# FPGA_7A35T.net
KiCad netlist of a schematic drawn in Altium Designer
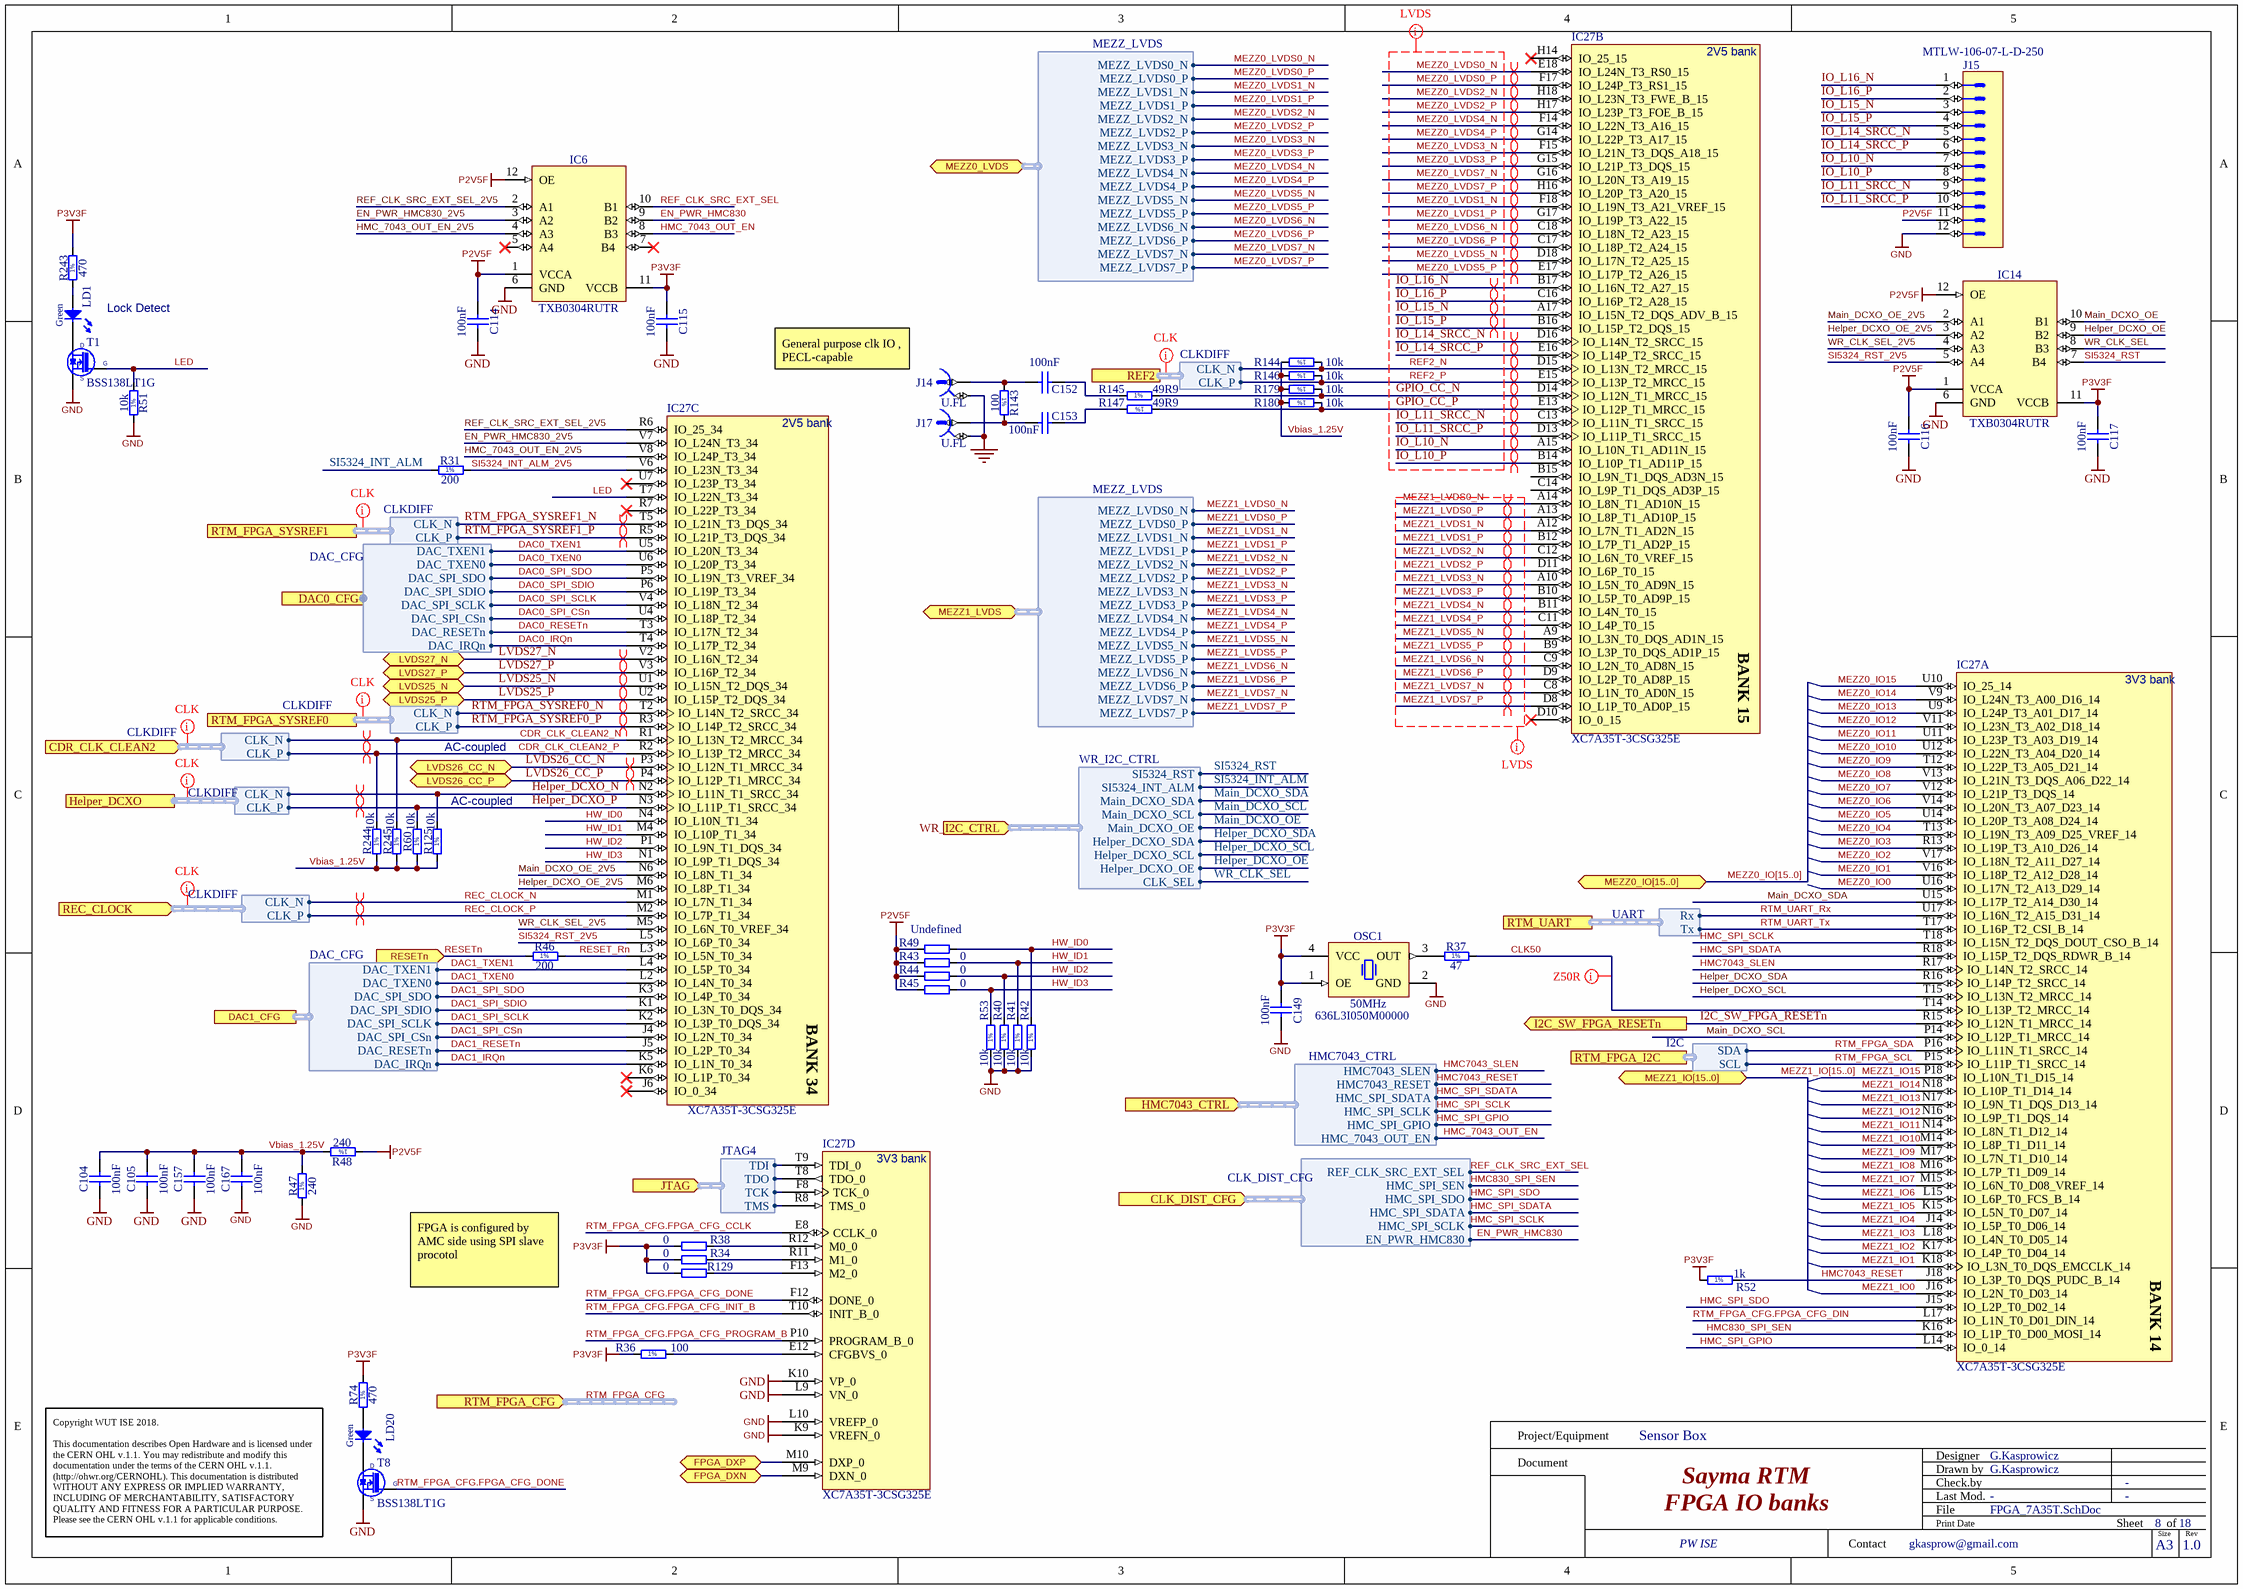
[diagram p0: FPGA_7A35T.SchDoc]

(export (version "E")
  (design (tool "Eeschema 10.0.6"))
  (components
    (comp (ref "C104")
      (value "100nF")
      (footprint "CAPC0603X33N")
      (description "Non-polarised capacitor")
      (fields
        (field (name "MANUFACTURER PART NUMBER") "CC0201_100NF_6.3V_10%_X5R")
        (field (name "MANUFACTURER") "GENERIC")
        (field (name "AUTHOR") "CERN DEM JLC")
      )
      (libsource (lib "Capacitors") (part "Capacitor - non polarized"))
    )
    (comp (ref "C105")
      (value "100nF")
      (footprint "CAPC0603X33N")
      (description "Non-polarised capacitor")
      (fields
        (field (name "MANUFACTURER PART NUMBER") "CC0201_100NF_6.3V_10%_X5R")
        (field (name "MANUFACTURER") "GENERIC")
        (field (name "AUTHOR") "CERN DEM JLC")
      )
      (libsource (lib "Capacitors") (part "Capacitor - non polarized"))
    )
    (comp (ref "C114")
      (value "100nF")
      (footprint "CAPC0603X33N")
      (description "Non-polarised capacitor")
      (fields
        (field (name "MANUFACTURER PART NUMBER") "CC0201_100NF_6.3V_10%_X5R")
        (field (name "MANUFACTURER") "GENERIC")
        (field (name "AUTHOR") "CERN DEM JLC")
      )
      (libsource (lib "Capacitors") (part "Capacitor - non polarized"))
    )
    (comp (ref "C115")
      (value "100nF")
      (footprint "CAPC0603X33N")
      (description "Non-polarised capacitor")
      (fields
        (field (name "MANUFACTURER PART NUMBER") "CC0201_100NF_6.3V_10%_X5R")
        (field (name "MANUFACTURER") "GENERIC")
        (field (name "AUTHOR") "CERN DEM JLC")
      )
      (libsource (lib "Capacitors") (part "Capacitor - non polarized"))
    )
    (comp (ref "C116")
      (value "100nF")
      (footprint "CAPC0603X33N")
      (description "Non-polarised capacitor")
      (fields
        (field (name "MANUFACTURER PART NUMBER") "CC0201_100NF_6.3V_10%_X5R")
        (field (name "MANUFACTURER") "GENERIC")
        (field (name "AUTHOR") "CERN DEM JLC")
      )
      (libsource (lib "Capacitors") (part "Capacitor - non polarized"))
    )
    (comp (ref "C117")
      (value "100nF")
      (footprint "CAPC0603X33N")
      (description "Non-polarised capacitor")
      (fields
        (field (name "MANUFACTURER PART NUMBER") "CC0201_100NF_6.3V_10%_X5R")
        (field (name "MANUFACTURER") "GENERIC")
        (field (name "AUTHOR") "CERN DEM JLC")
      )
      (libsource (lib "Capacitors") (part "Capacitor - non polarized"))
    )
    (comp (ref "C149")
      (value "100nF")
      (footprint "CAPC0603X33N")
      (description "Non-polarised capacitor")
      (fields
        (field (name "MANUFACTURER PART NUMBER") "CC0201_100NF_6.3V_10%_X5R")
        (field (name "MANUFACTURER") "GENERIC")
        (field (name "AUTHOR") "CERN DEM JLC")
      )
      (libsource (lib "Capacitors") (part "Capacitor - non polarized"))
    )
    (comp (ref "C152")
      (value "100nF")
      (footprint "CAPC1005X55N")
      (description "Non-polarised capacitor")
      (fields
        (field (name "MANUFACTURER PART NUMBER") "CC0402_100NF_16V_10%_X5R")
        (field (name "MANUFACTURER") "GENERIC")
        (field (name "AUTHOR") "CERN DEM JLC")
      )
      (libsource (lib "Capacitors") (part "Capacitor - non polarized"))
    )
    (comp (ref "C153")
      (value "100nF")
      (footprint "CAPC1005X55N")
      (description "Non-polarised capacitor")
      (fields
        (field (name "MANUFACTURER PART NUMBER") "CC0402_100NF_16V_10%_X5R")
        (field (name "MANUFACTURER") "GENERIC")
        (field (name "AUTHOR") "CERN DEM JLC")
      )
      (libsource (lib "Capacitors") (part "Capacitor - non polarized"))
    )
    (comp (ref "C157")
      (value "100nF")
      (footprint "CAPC0603X33N")
      (description "Non-polarised capacitor")
      (fields
        (field (name "MANUFACTURER PART NUMBER") "CC0201_100NF_6.3V_10%_X5R")
        (field (name "MANUFACTURER") "GENERIC")
        (field (name "AUTHOR") "CERN DEM JLC")
      )
      (libsource (lib "Capacitors") (part "Capacitor - non polarized"))
    )
    (comp (ref "C167")
      (value "100nF")
      (footprint "CAPC0603X33N")
      (description "Non-polarised capacitor")
      (fields
        (field (name "MANUFACTURER PART NUMBER") "CC0201_100NF_6.3V_10%_X5R")
        (field (name "MANUFACTURER") "GENERIC")
        (field (name "AUTHOR") "CERN DEM JLC")
      )
      (libsource (lib "Capacitors") (part "Capacitor - non polarized"))
    )
    (comp (ref "IC6")
      (value "TXB0304RUTR")
      (footprint "TEXAS_RUT (R-PUQFN-N12)")
      (description "4-bit Bidirectional Auto-direction Sensing Translator with Fully Symmetric 0.9V to 3.6V Range")
      (fields (field (name "MANUFACTURER") "TEXAS INSTRUMENTS") (field (name "AUTHOR") "CERN DEM JLC"))
      (libsource (lib "ICs And Semiconductors") (part "TXB0304RUTR"))
    )
    (comp (ref "IC14")
      (value "TXB0304RUTR")
      (footprint "TEXAS_RUT (R-PUQFN-N12)")
      (description "4-bit Bidirectional Auto-direction Sensing Translator with Fully Symmetric 0.9V to 3.6V Range")
      (fields (field (name "MANUFACTURER") "TEXAS INSTRUMENTS") (field (name "AUTHOR") "CERN DEM JLC"))
      (libsource (lib "ICs And Semiconductors") (part "TXB0304RUTR"))
    )
    (comp (ref "IC27")
      (value "XC7A35T-3CSG325E")
      (footprint "CSG325")
      (description "Artix-7 FPGA, 150 User I/Os, 4 GTP, 324-Ball BGA, Speed Grade 3, Extended Grade, Pb-Free")
      (fields (field (name "MANUFACTURER") "Xilinx"))
      (libsource (lib "") (part "XLNX-XC7A35T-CSG325_1"))
    )
    (comp (ref "J14")
      (value "U.FL")
      (footprint "HIROSE_U.FL-R-SMT-1(10)")
      (fields
        (field (name "PART NUMBER") "HIROSE_U.FL-R-SMT-1(10)")
        (field (name "MANUFACTURER") "HIROSE (HRS)")
        (field (name "MANUFACTURER PART NUMBER") "U.FL-R-SMT-1(10)")
        (field (name "AUTHOR") "CERN DEM JLC")
      )
      (libsource (lib "Connectors") (part "Coax_1Male_1Shield"))
    )
    (comp (ref "J15")
      (value "Header 12")
      (footprint "SAMTEC_MTLW-106-07-L-D-250")
      (description "Connector 12 Male")
      (fields
        (field (name "MANUFACTURER PART NUMBER") "MTLW-106-07-L-D-250")
        (field (name "MANUFACTURER") "SAMTEC")
        (field (name "PART NUMBER") "SAMTEC_MTLW-106-07-L-D-250")
        (field (name "AUTHOR") "CERN DEM JLC")
      )
      (libsource (lib "Connectors") (part "Connector 12 Male"))
    )
    (comp (ref "J17")
      (value "U.FL")
      (footprint "HIROSE_U.FL-R-SMT-1(10)")
      (fields
        (field (name "PART NUMBER") "HIROSE_U.FL-R-SMT-1(10)")
        (field (name "MANUFACTURER") "HIROSE (HRS)")
        (field (name "MANUFACTURER PART NUMBER") "U.FL-R-SMT-1(10)")
        (field (name "AUTHOR") "CERN DEM JLC")
      )
      (libsource (lib "Connectors") (part "Coax_1Male_1Shield"))
    )
    (comp (ref "LD1")
      (value "Green")
      (footprint "LED_KINGBRIGHT_KPH-1608CGCK")
      (description "LED Green 1C 2A")
      (fields
        (field (name "MANUFACTURER PART NUMBER") "KPH-1608CGCK")
        (field (name "MANUFACTURER") "KINGBRIGHT")
        (field (name "AUTHOR") "CERN DEM JLC")
      )
      (libsource (lib "ICs And Semiconductors") (part "LED Green 1C 2A"))
    )
    (comp (ref "LD20")
      (value "Green")
      (footprint "LED_KINGBRIGHT_KPH-1608CGCK")
      (description "LED Green 1C 2A")
      (fields
        (field (name "MANUFACTURER PART NUMBER") "KPH-1608CGCK")
        (field (name "MANUFACTURER") "KINGBRIGHT")
        (field (name "AUTHOR") "CERN DEM JLC")
      )
      (libsource (lib "ICs And Semiconductors") (part "LED Green 1C 2A"))
    )
    (comp (ref "OSC1")
      (value "50MHz")
      (footprint "OSCSC254P320X500X130-4N")
      (description "Oscillator 4 pins 1=OE 2=GND 3=OUT 4=VCC")
      (fields
        (field (name "MANUFACTURER PART NUMBER") "636L3I050M00000")
        (field (name "MANUFACTURER") "CTS ELECTRONIC COMPONENTS")
        (field (name "PART NUMBER") "OSC_50MHZ_CTS_636L3I050M00000")
        (field (name "AUTHOR") "CERN DEM JMW")
      )
      (libsource (lib "ICs And Semiconductors") (part "Oscillator 1OE 2GND 3OUT 4VCC"))
    )
    (comp (ref "R31")
      (value "200")
      (footprint "RESC1005X40N")
      (description "Resistor - 1%")
      (fields
        (field (name "MANUFACTURER PART NUMBER") "R0402_200R_1%_0.0625W_100PPM")
        (field (name "MANUFACTURER") "GENERIC")
        (field (name "AUTHOR") "CERN DEM JLC")
      )
      (libsource (lib "Resistors") (part "Resistor - 1%"))
    )
    (comp (ref "R34")
      (value "0")
      (footprint "RESC1005X40N")
      (description "Resistor")
      (fields
        (field (name "MANUFACTURER PART NUMBER") "R0402_0R_JUMPER")
        (field (name "MANUFACTURER") "GENERIC")
        (field (name "AUTHOR") "CERN DEM JLC")
      )
      (libsource (lib "Resistors") (part "Resistor"))
    )
    (comp (ref "R36")
      (value "100")
      (footprint "RESC1005X40N")
      (description "Resistor - 1%")
      (fields
        (field (name "MANUFACTURER PART NUMBER") "R0402_100R_1%_0.1W_100PPM_50V")
        (field (name "MANUFACTURER") "GENERIC")
        (field (name "AUTHOR") "CERN DEM JLC")
      )
      (libsource (lib "Resistors") (part "Resistor - 1%"))
    )
    (comp (ref "R37")
      (value "47")
      (footprint "RESC1005X40N")
      (description "Resistor - 1%")
      (fields
        (field (name "PART NUMBER") "R0402_47R_1%_0.0625W_100PPM")
        (field (name "POWER") "0.0625W")
        (field (name "AUTHOR") "CERN DEM JLC")
      )
      (libsource (lib "Resistors") (part "Resistor - 1%"))
    )
    (comp (ref "R38")
      (value "0")
      (footprint "RESC1005X40N")
      (description "Resistor")
      (fields
        (field (name "MANUFACTURER PART NUMBER") "R0402_0R_JUMPER")
        (field (name "MANUFACTURER") "GENERIC")
        (field (name "AUTHOR") "CERN DEM JLC")
      )
      (libsource (lib "Resistors") (part "Resistor"))
    )
    (comp (ref "R40")
      (value "10k")
      (footprint "RESC1005X40N")
      (description "Resistor - 1%")
      (fields
        (field (name "MANUFACTURER PART NUMBER") "R0402_10K_1%_0.0625W_100PPM")
        (field (name "MANUFACTURER") "GENERIC")
        (field (name "AUTHOR") "CERN DEM JLC")
      )
      (libsource (lib "Resistors") (part "Resistor - 1%"))
    )
    (comp (ref "R41")
      (value "10k")
      (footprint "RESC1005X40N")
      (description "Resistor - 1%")
      (fields
        (field (name "MANUFACTURER PART NUMBER") "R0402_10K_1%_0.0625W_100PPM")
        (field (name "MANUFACTURER") "GENERIC")
        (field (name "AUTHOR") "CERN DEM JLC")
      )
      (libsource (lib "Resistors") (part "Resistor - 1%"))
    )
    (comp (ref "R42")
      (value "10k")
      (footprint "RESC1005X40N")
      (description "Resistor - 1%")
      (fields
        (field (name "MANUFACTURER PART NUMBER") "R0402_10K_1%_0.0625W_100PPM")
        (field (name "MANUFACTURER") "GENERIC")
        (field (name "AUTHOR") "CERN DEM JLC")
      )
      (libsource (lib "Resistors") (part "Resistor - 1%"))
    )
    (comp (ref "R43")
      (value "0")
      (footprint "RESC1005X40N")
      (description "Resistor")
      (fields
        (field (name "MANUFACTURER PART NUMBER") "R0402_0R_JUMPER")
        (field (name "MANUFACTURER") "GENERIC")
        (field (name "AUTHOR") "CERN DEM JLC")
      )
      (libsource (lib "Resistors") (part "Resistor"))
    )
    (comp (ref "R44")
      (value "0")
      (footprint "RESC1005X40N")
      (description "Resistor")
      (fields
        (field (name "MANUFACTURER PART NUMBER") "R0402_0R_JUMPER")
        (field (name "MANUFACTURER") "GENERIC")
        (field (name "AUTHOR") "CERN DEM JLC")
      )
      (libsource (lib "Resistors") (part "Resistor"))
    )
    (comp (ref "R45")
      (value "0")
      (footprint "RESC1005X40N")
      (description "Resistor")
      (fields
        (field (name "MANUFACTURER PART NUMBER") "R0402_0R_JUMPER")
        (field (name "MANUFACTURER") "GENERIC")
        (field (name "AUTHOR") "CERN DEM JLC")
      )
      (libsource (lib "Resistors") (part "Resistor"))
    )
    (comp (ref "R46")
      (value "200")
      (footprint "RESC1005X40N")
      (description "Resistor - 1%")
      (fields
        (field (name "MANUFACTURER PART NUMBER") "R0402_200R_1%_0.0625W_100PPM")
        (field (name "MANUFACTURER") "GENERIC")
        (field (name "AUTHOR") "CERN DEM JLC")
      )
      (libsource (lib "Resistors") (part "Resistor - 1%"))
    )
    (comp (ref "R47")
      (value "240")
      (footprint "RESC1005X40N")
      (description "Resistor - 1%")
      (fields
        (field (name "MANUFACTURER PART NUMBER") "R0402_240R_1%_0.0625W_100PPM")
        (field (name "MANUFACTURER") "GENERIC")
        (field (name "AUTHOR") "CERN DEM JLC")
      )
      (libsource (lib "Resistors") (part "Resistor - 1%"))
    )
    (comp (ref "R48")
      (value "240")
      (footprint "RESC1005X40N")
      (description "Resistor - 1%")
      (fields
        (field (name "MANUFACTURER PART NUMBER") "R0402_240R_1%_0.0625W_100PPM")
        (field (name "MANUFACTURER") "GENERIC")
        (field (name "AUTHOR") "CERN DEM JLC")
      )
      (libsource (lib "Resistors") (part "Resistor - 1%"))
    )
    (comp (ref "R49")
      (value "Undefined")
      (footprint "RESC1005X40N")
      (description "Resistor")
      (fields
        (field (name "MANUFACTURER PART NUMBER") "R0402_NO-VALUE")
        (field (name "AUTHOR") "CERN DEM JLC")
      )
      (libsource (lib "Resistors") (part "Resistor"))
    )
    (comp (ref "R51")
      (value "10k")
      (footprint "RESC1005X40N")
      (description "Resistor - 1%")
      (fields
        (field (name "MANUFACTURER PART NUMBER") "R0402_10K_1%_0.0625W_100PPM")
        (field (name "MANUFACTURER") "GENERIC")
        (field (name "AUTHOR") "CERN DEM JLC")
      )
      (libsource (lib "Resistors") (part "Resistor - 1%"))
    )
    (comp (ref "R52")
      (value "1k")
      (footprint "RESC1005X40N")
      (description "Resistor - 1%")
      (fields
        (field (name "MANUFACTURER PART NUMBER") "R0402_1K_1%_0.0625W_100PPM")
        (field (name "MANUFACTURER") "GENERIC")
        (field (name "AUTHOR") "CERN DEM JLC")
      )
      (libsource (lib "Resistors") (part "Resistor - 1%"))
    )
    (comp (ref "R53")
      (value "10k")
      (footprint "RESC1005X40N")
      (description "Resistor - 1%")
      (fields
        (field (name "MANUFACTURER PART NUMBER") "R0402_10K_1%_0.0625W_100PPM")
        (field (name "MANUFACTURER") "GENERIC")
        (field (name "AUTHOR") "CERN DEM JLC")
      )
      (libsource (lib "Resistors") (part "Resistor - 1%"))
    )
    (comp (ref "R60")
      (value "10k")
      (footprint "RESC1005X40N")
      (description "Resistor - 1%")
      (fields
        (field (name "MANUFACTURER PART NUMBER") "R0402_10K_1%_0.0625W_100PPM")
        (field (name "MANUFACTURER") "GENERIC")
        (field (name "AUTHOR") "CERN DEM JLC")
      )
      (libsource (lib "Resistors") (part "Resistor - 1%"))
    )
    (comp (ref "R74")
      (value "470")
      (footprint "RESC1005X40N")
      (description "Resistor - 1%")
      (fields
        (field (name "MANUFACTURER PART NUMBER") "R0402_470R_1%_0.0625W_100PPM")
        (field (name "MANUFACTURER") "GENERIC")
        (field (name "AUTHOR") "CERN DEM JLC")
      )
      (libsource (lib "Resistors") (part "Resistor - 1%"))
    )
    (comp (ref "R125")
      (value "10k")
      (footprint "RESC1005X40N")
      (description "Resistor - 1%")
      (fields
        (field (name "MANUFACTURER PART NUMBER") "R0402_10K_1%_0.0625W_100PPM")
        (field (name "MANUFACTURER") "GENERIC")
        (field (name "AUTHOR") "CERN DEM JLC")
      )
      (libsource (lib "Resistors") (part "Resistor - 1%"))
    )
    (comp (ref "R129")
      (value "0")
      (footprint "RESC1005X40N")
      (description "Resistor")
      (fields
        (field (name "MANUFACTURER PART NUMBER") "R0402_0R_JUMPER")
        (field (name "MANUFACTURER") "GENERIC")
        (field (name "AUTHOR") "CERN DEM JLC")
      )
      (libsource (lib "Resistors") (part "Resistor"))
    )
    (comp (ref "R143")
      (value "100")
      (footprint "RESC1005X40N")
      (description "Resistor - 1%")
      (fields
        (field (name "MANUFACTURER PART NUMBER") "R0402_100R_1%_0.0625W_100PPM")
        (field (name "MANUFACTURER") "GENERIC")
        (field (name "AUTHOR") "CERN DEM JLC")
      )
      (libsource (lib "Resistors") (part "Resistor - 1%"))
    )
    (comp (ref "R144")
      (value "10k")
      (footprint "RESC1005X40N")
      (description "Resistor - 1%")
      (fields
        (field (name "MANUFACTURER PART NUMBER") "R0402_10K_1%_0.0625W_100PPM")
        (field (name "MANUFACTURER") "GENERIC")
        (field (name "AUTHOR") "CERN DEM JLC")
      )
      (libsource (lib "Resistors") (part "Resistor - 1%"))
    )
    (comp (ref "R145")
      (value "49R9")
      (footprint "RESC1005X40N")
      (description "Resistor - 1%")
      (fields
        (field (name "MANUFACTURER PART NUMBER") "R0402_49R9_1%_0.0625W_100PPM")
        (field (name "MANUFACTURER") "GENERIC")
        (field (name "AUTHOR") "CERN DEM JLC")
      )
      (libsource (lib "Resistors") (part "Resistor - 1%"))
    )
    (comp (ref "R146")
      (value "10k")
      (footprint "RESC1005X40N")
      (description "Resistor - 1%")
      (fields
        (field (name "MANUFACTURER PART NUMBER") "R0402_10K_1%_0.0625W_100PPM")
        (field (name "MANUFACTURER") "GENERIC")
        (field (name "AUTHOR") "CERN DEM JLC")
      )
      (libsource (lib "Resistors") (part "Resistor - 1%"))
    )
    (comp (ref "R147")
      (value "49R9")
      (footprint "RESC1005X40N")
      (description "Resistor - 1%")
      (fields
        (field (name "MANUFACTURER PART NUMBER") "R0402_49R9_1%_0.0625W_100PPM")
        (field (name "MANUFACTURER") "GENERIC")
        (field (name "AUTHOR") "CERN DEM JLC")
      )
      (libsource (lib "Resistors") (part "Resistor - 1%"))
    )
    (comp (ref "R179")
      (value "10k")
      (footprint "RESC1005X40N")
      (description "Resistor - 1%")
      (fields
        (field (name "MANUFACTURER PART NUMBER") "R0402_10K_1%_0.0625W_100PPM")
        (field (name "MANUFACTURER") "GENERIC")
        (field (name "AUTHOR") "CERN DEM JLC")
      )
      (libsource (lib "Resistors") (part "Resistor - 1%"))
    )
    (comp (ref "R180")
      (value "10k")
      (footprint "RESC1005X40N")
      (description "Resistor - 1%")
      (fields
        (field (name "MANUFACTURER PART NUMBER") "R0402_10K_1%_0.0625W_100PPM")
        (field (name "MANUFACTURER") "GENERIC")
        (field (name "AUTHOR") "CERN DEM JLC")
      )
      (libsource (lib "Resistors") (part "Resistor - 1%"))
    )
    (comp (ref "R243")
      (value "470")
      (footprint "RESC1005X40N")
      (description "Resistor - 1%")
      (fields
        (field (name "MANUFACTURER PART NUMBER") "R0402_470R_1%_0.0625W_100PPM")
        (field (name "MANUFACTURER") "GENERIC")
        (field (name "AUTHOR") "CERN DEM JLC")
      )
      (libsource (lib "Resistors") (part "Resistor - 1%"))
    )
    (comp (ref "R244")
      (value "10k")
      (footprint "RESC1005X40N")
      (description "Resistor - 1%")
      (fields
        (field (name "MANUFACTURER PART NUMBER") "R0402_10K_1%_0.0625W_100PPM")
        (field (name "MANUFACTURER") "GENERIC")
        (field (name "AUTHOR") "CERN DEM JLC")
      )
      (libsource (lib "Resistors") (part "Resistor - 1%"))
    )
    (comp (ref "R245")
      (value "10k")
      (footprint "RESC1005X40N")
      (description "Resistor - 1%")
      (fields
        (field (name "MANUFACTURER PART NUMBER") "R0402_10K_1%_0.0625W_100PPM")
        (field (name "MANUFACTURER") "GENERIC")
        (field (name "AUTHOR") "CERN DEM JLC")
      )
      (libsource (lib "Resistors") (part "Resistor - 1%"))
    )
    (comp (ref "T1")
      (value "BSS138LT1G")
      (footprint "SOT95P240X110-3N")
      (description "N-CHANNEL MOSFET WITH DIODE")
      (fields (field (name "MANUFACTURER") "ON SEMICONDUCTOR") (field (name "AUTHOR") "CERN DEM JLC"))
      (libsource (lib "ICs And Semiconductors") (part "N-MOSFET-D 1G 2S 3D"))
    )
    (comp (ref "T8")
      (value "BSS138LT1G")
      (footprint "SOT95P240X110-3N")
      (description "N-CHANNEL MOSFET WITH DIODE")
      (fields (field (name "MANUFACTURER") "ON SEMICONDUCTOR") (field (name "AUTHOR") "CERN DEM JLC"))
      (libsource (lib "ICs And Semiconductors") (part "N-MOSFET-D 1G 2S 3D"))
    )
  )
  (nets
    (net (code "11") (name "/CDR_CLK_CLEAN2_N") (class "Default")
      (node (ref "IC27") (pin "R1") (pinfunction "IO_L13N_T2_MRCC_34_R1") (pintype "bidirectional"))
      (node (ref "R245") (pin "2") (pinfunction "2_2") (pintype "passive"))
    )
    (net (code "12") (name "/CDR_CLK_CLEAN2_P") (class "Default")
      (node (ref "IC27") (pin "R2") (pinfunction "IO_L13P_T2_MRCC_34_R2") (pintype "bidirectional"))
      (node (ref "R244") (pin "2") (pinfunction "2_2") (pintype "passive"))
    )
    (net (code "13") (name "/CLK50") (class "Default")
      (node (ref "IC27") (pin "T14") (pinfunction "IO_L13P_T2_MRCC_14_T14") (pintype "bidirectional"))
      (node (ref "R37") (pin "2") (pinfunction "2_2") (pintype "passive"))
    )
    (net (code "14") (name "/DAC0_IRQn") (class "Default")
      (node (ref "IC27") (pin "T4") (pinfunction "IO_L17P_T2_34_T4") (pintype "bidirectional"))
    )
    (net (code "15") (name "/DAC0_RESETn") (class "Default")
      (node (ref "IC27") (pin "T3") (pinfunction "IO_L17N_T2_34_T3") (pintype "bidirectional"))
    )
    (net (code "16") (name "/DAC0_SPI_CSn") (class "Default")
      (node (ref "IC27") (pin "U4") (pinfunction "IO_L18P_T2_34_U4") (pintype "bidirectional"))
    )
    (net (code "17") (name "/DAC0_SPI_SCLK") (class "Default")
      (node (ref "IC27") (pin "V4") (pinfunction "IO_L18N_T2_34_V4") (pintype "bidirectional"))
    )
    (net (code "18") (name "/DAC0_SPI_SDIO") (class "Default")
      (node (ref "IC27") (pin "P6") (pinfunction "IO_L19P_T3_34_P6") (pintype "bidirectional"))
    )
    (net (code "19") (name "/DAC0_SPI_SDO") (class "Default")
      (node (ref "IC27") (pin "P5") (pinfunction "IO_L19N_T3_VREF_34_P5") (pintype "bidirectional"))
    )
    (net (code "20") (name "/DAC0_TXEN0") (class "Default")
      (node (ref "IC27") (pin "U6") (pinfunction "IO_L20P_T3_34_U6") (pintype "bidirectional"))
    )
    (net (code "21") (name "/DAC0_TXEN1") (class "Default")
      (node (ref "IC27") (pin "U5") (pinfunction "IO_L20N_T3_34_U5") (pintype "bidirectional"))
    )
    (net (code "22") (name "/DAC1_IRQn") (class "Default")
      (node (ref "IC27") (pin "K5") (pinfunction "IO_L1N_T0_34_K5") (pintype "bidirectional"))
    )
    (net (code "23") (name "/DAC1_RESETn") (class "Default")
      (node (ref "IC27") (pin "J5") (pinfunction "IO_L2P_T0_34_J5") (pintype "bidirectional"))
    )
    (net (code "24") (name "/DAC1_SPI_CSn") (class "Default")
      (node (ref "IC27") (pin "J4") (pinfunction "IO_L2N_T0_34_J4") (pintype "bidirectional"))
    )
    (net (code "25") (name "/DAC1_SPI_SCLK") (class "Default")
      (node (ref "IC27") (pin "K2") (pinfunction "IO_L3P_T0_DQS_34_K2") (pintype "bidirectional"))
    )
    (net (code "26") (name "/DAC1_SPI_SDIO") (class "Default")
      (node (ref "IC27") (pin "K1") (pinfunction "IO_L3N_T0_DQS_34_K1") (pintype "bidirectional"))
    )
    (net (code "27") (name "/DAC1_SPI_SDO") (class "Default")
      (node (ref "IC27") (pin "K3") (pinfunction "IO_L4P_T0_34_K3") (pintype "bidirectional"))
    )
    (net (code "28") (name "/DAC1_TXEN0") (class "Default")
      (node (ref "IC27") (pin "L2") (pinfunction "IO_L4N_T0_34_L2") (pintype "bidirectional"))
    )
    (net (code "29") (name "/DAC1_TXEN1") (class "Default")
      (node (ref "IC27") (pin "L4") (pinfunction "IO_L5P_T0_34_L4") (pintype "bidirectional"))
    )
    (net (code "30") (name "/EN_PWR_HMC830") (class "Default")
      (node (ref "IC6") (pin "9") (pinfunction "B2_9") (pintype "bidirectional"))
    )
    (net (code "31") (name "/EN_PWR_HMC830_2V5") (class "Default")
      (node (ref "IC27") (pin "V7") (pinfunction "IO_L24N_T3_34_V7") (pintype "bidirectional"))
      (node (ref "IC6") (pin "3") (pinfunction "A2_3") (pintype "bidirectional"))
    )
    (net (code "32") (name "/FPGA_DXN") (class "Default")
      (node (ref "IC27") (pin "M9") (pinfunction "DXN_0_M9") (pintype "input"))
    )
    (net (code "33") (name "/FPGA_DXP") (class "Default")
      (node (ref "IC27") (pin "M10") (pinfunction "DXP_0_M10") (pintype "input"))
    )
    (net (code "34") (name "/GPIO_CC_N") (class "Default")
      (node (ref "IC27") (pin "D14") (pinfunction "IO_L12N_T1_MRCC_15_D14") (pintype "bidirectional"))
      (node (ref "R145") (pin "2") (pinfunction "2_2") (pintype "passive"))
      (node (ref "R179") (pin "1") (pinfunction "1_1") (pintype "passive"))
    )
    (net (code "35") (name "/GPIO_CC_P") (class "Default")
      (node (ref "IC27") (pin "E13") (pinfunction "IO_L12P_T1_MRCC_15_E13") (pintype "bidirectional"))
      (node (ref "R147") (pin "1") (pinfunction "1_1") (pintype "passive"))
      (node (ref "R180") (pin "1") (pinfunction "1_1") (pintype "passive"))
    )
    (net (code "36") (name "/HMC830_SPI_SEN") (class "Default")
      (node (ref "IC27") (pin "K16") (pinfunction "IO_L1P_T0_D00_MOSI_14_K16") (pintype "bidirectional"))
    )
    (net (code "37") (name "/HMC7043_RESET") (class "Default")
      (node (ref "IC27") (pin "J18") (pinfunction "IO_L3P_T0_DQS_PUDC_B_14_J18") (pintype "bidirectional"))
      (node (ref "R52") (pin "2") (pinfunction "2_2") (pintype "passive"))
    )
    (net (code "38") (name "/HMC7043_SLEN") (class "Default")
      (node (ref "IC27") (pin "R17") (pinfunction "IO_L14N_T2_SRCC_14_R17") (pintype "bidirectional"))
    )
    (net (code "39") (name "/HMC_7043_OUT_EN") (class "Default")
      (node (ref "IC6") (pin "8") (pinfunction "B3_8") (pintype "bidirectional"))
    )
    (net (code "40") (name "/HMC_7043_OUT_EN_2V5") (class "Default")
      (node (ref "IC27") (pin "V8") (pinfunction "IO_L24P_T3_34_V8") (pintype "bidirectional"))
      (node (ref "IC6") (pin "4") (pinfunction "A3_4") (pintype "bidirectional"))
    )
    (net (code "41") (name "/HMC_SPI_GPIO") (class "Default")
      (node (ref "IC27") (pin "L14") (pinfunction "IO_0_14_L14") (pintype "bidirectional"))
    )
    (net (code "42") (name "/HMC_SPI_SCLK") (class "Default")
      (node (ref "IC27") (pin "T18") (pinfunction "IO_L15N_T2_DQS_DOUT_CSO_B_14_T18") (pintype "bidirectional"))
    )
    (net (code "43") (name "/HMC_SPI_SDATA") (class "Default")
      (node (ref "IC27") (pin "R18") (pinfunction "IO_L15P_T2_DQS_RDWR_B_14_R18") (pintype "bidirectional"))
    )
    (net (code "44") (name "/HMC_SPI_SDO") (class "Default")
      (node (ref "IC27") (pin "J15") (pinfunction "IO_L2P_T0_D02_14_J15") (pintype "bidirectional"))
    )
    (net (code "45") (name "/HW_ID0") (class "Default")
      (node (ref "IC27") (pin "N4") (pinfunction "IO_L10N_T1_34_N4") (pintype "bidirectional"))
      (node (ref "R42") (pin "2") (pinfunction "2_2") (pintype "passive"))
      (node (ref "R49") (pin "2") (pinfunction "2_2") (pintype "passive"))
    )
    (net (code "46") (name "/HW_ID1") (class "Default")
      (node (ref "IC27") (pin "M4") (pinfunction "IO_L10P_T1_34_M4") (pintype "bidirectional"))
      (node (ref "R41") (pin "2") (pinfunction "2_2") (pintype "passive"))
      (node (ref "R43") (pin "2") (pinfunction "2_2") (pintype "passive"))
    )
    (net (code "47") (name "/HW_ID2") (class "Default")
      (node (ref "IC27") (pin "P1") (pinfunction "IO_L9N_T1_DQS_34_P1") (pintype "bidirectional"))
      (node (ref "R40") (pin "2") (pinfunction "2_2") (pintype "passive"))
      (node (ref "R44") (pin "2") (pinfunction "2_2") (pintype "passive"))
    )
    (net (code "48") (name "/HW_ID3") (class "Default")
      (node (ref "IC27") (pin "N1") (pinfunction "IO_L9P_T1_DQS_34_N1") (pintype "bidirectional"))
      (node (ref "R45") (pin "2") (pinfunction "2_2") (pintype "passive"))
      (node (ref "R53") (pin "2") (pinfunction "2_2") (pintype "passive"))
    )
    (net (code "49") (name "/Helper_DCXO_N") (class "Default")
      (node (ref "IC27") (pin "N2") (pinfunction "IO_L11N_T1_SRCC_34_N2") (pintype "bidirectional"))
      (node (ref "R125") (pin "2") (pinfunction "2_2") (pintype "passive"))
    )
    (net (code "50") (name "/Helper_DCXO_OE") (class "Default")
      (node (ref "IC14") (pin "9") (pinfunction "B2_9") (pintype "bidirectional"))
    )
    (net (code "51") (name "/Helper_DCXO_OE_2V5") (class "Default")
      (node (ref "IC14") (pin "3") (pinfunction "A2_3") (pintype "bidirectional"))
      (node (ref "IC27") (pin "M6") (pinfunction "IO_L8P_T1_34_M6") (pintype "bidirectional"))
    )
    (net (code "52") (name "/Helper_DCXO_P") (class "Default")
      (node (ref "IC27") (pin "N3") (pinfunction "IO_L11P_T1_SRCC_34_N3") (pintype "bidirectional"))
      (node (ref "R60") (pin "2") (pinfunction "2_2") (pintype "passive"))
    )
    (net (code "53") (name "/Helper_DCXO_SCL") (class "Default")
      (node (ref "IC27") (pin "T15") (pinfunction "IO_L13N_T2_MRCC_14_T15") (pintype "bidirectional"))
    )
    (net (code "54") (name "/Helper_DCXO_SDA") (class "Default")
      (node (ref "IC27") (pin "R16") (pinfunction "IO_L14P_T2_SRCC_14_R16") (pintype "bidirectional"))
    )
    (net (code "55") (name "/I2C_SW_FPGA_RESETn") (class "Default")
      (node (ref "IC27") (pin "R15") (pinfunction "IO_L12N_T1_MRCC_14_R15") (pintype "bidirectional"))
    )
    (net (code "56") (name "/IO_L10_N") (class "Default")
      (node (ref "IC27") (pin "A15") (pinfunction "IO_L10N_T1_AD11N_15_A15") (pintype "bidirectional"))
      (node (ref "J15") (pin "7") (pinfunction "7_7") (pintype "bidirectional"))
    )
    (net (code "57") (name "/IO_L10_P") (class "Default")
      (node (ref "IC27") (pin "B14") (pinfunction "IO_L10P_T1_AD11P_15_B14") (pintype "bidirectional"))
      (node (ref "J15") (pin "8") (pinfunction "8_8") (pintype "bidirectional"))
    )
    (net (code "58") (name "/IO_L11_SRCC_N") (class "Default")
      (node (ref "IC27") (pin "C13") (pinfunction "IO_L11N_T1_SRCC_15_C13") (pintype "bidirectional"))
      (node (ref "J15") (pin "9") (pinfunction "9_9") (pintype "bidirectional"))
    )
    (net (code "59") (name "/IO_L11_SRCC_P") (class "Default")
      (node (ref "IC27") (pin "D13") (pinfunction "IO_L11P_T1_SRCC_15_D13") (pintype "bidirectional"))
      (node (ref "J15") (pin "10") (pinfunction "10_10") (pintype "bidirectional"))
    )
    (net (code "60") (name "/IO_L14_SRCC_N") (class "Default")
      (node (ref "IC27") (pin "D16") (pinfunction "IO_L14N_T2_SRCC_15_D16") (pintype "bidirectional"))
      (node (ref "J15") (pin "5") (pinfunction "5_5") (pintype "bidirectional"))
    )
    (net (code "61") (name "/IO_L14_SRCC_P") (class "Default")
      (node (ref "IC27") (pin "E16") (pinfunction "IO_L14P_T2_SRCC_15_E16") (pintype "bidirectional"))
      (node (ref "J15") (pin "6") (pinfunction "6_6") (pintype "bidirectional"))
    )
    (net (code "62") (name "/IO_L15_N") (class "Default")
      (node (ref "IC27") (pin "A17") (pinfunction "IO_L15N_T2_DQS_ADV_B_15_A17") (pintype "bidirectional"))
      (node (ref "J15") (pin "3") (pinfunction "3_3") (pintype "bidirectional"))
    )
    (net (code "63") (name "/IO_L15_P") (class "Default")
      (node (ref "IC27") (pin "B16") (pinfunction "IO_L15P_T2_DQS_15_B16") (pintype "bidirectional"))
      (node (ref "J15") (pin "4") (pinfunction "4_4") (pintype "bidirectional"))
    )
    (net (code "64") (name "/IO_L16_N") (class "Default")
      (node (ref "IC27") (pin "B17") (pinfunction "IO_L16N_T2_A27_15_B17") (pintype "bidirectional"))
      (node (ref "J15") (pin "1") (pinfunction "1_1") (pintype "bidirectional"))
    )
    (net (code "65") (name "/IO_L16_P") (class "Default")
      (node (ref "IC27") (pin "C16") (pinfunction "IO_L16P_T2_A28_15_C16") (pintype "bidirectional"))
      (node (ref "J15") (pin "2") (pinfunction "2_2") (pintype "bidirectional"))
    )
    (net (code "66") (name "/LED") (class "Default")
      (node (ref "IC27") (pin "T7") (pinfunction "IO_L22N_T3_34_T7") (pintype "bidirectional"))
      (node (ref "R51") (pin "2") (pinfunction "2_2") (pintype "passive"))
      (node (ref "T1") (pin "1") (pinfunction "G_1") (pintype "passive"))
    )
    (net (code "67") (name "/LVDS25_N") (class "Default")
      (node (ref "IC27") (pin "U1") (pinfunction "IO_L15N_T2_DQS_34_U1") (pintype "bidirectional"))
    )
    (net (code "68") (name "/LVDS25_P") (class "Default")
      (node (ref "IC27") (pin "U2") (pinfunction "IO_L15P_T2_DQS_34_U2") (pintype "bidirectional"))
    )
    (net (code "69") (name "/LVDS26_CC_N") (class "Default")
      (node (ref "IC27") (pin "P3") (pinfunction "IO_L12N_T1_MRCC_34_P3") (pintype "bidirectional"))
    )
    (net (code "70") (name "/LVDS26_CC_P") (class "Default")
      (node (ref "IC27") (pin "P4") (pinfunction "IO_L12P_T1_MRCC_34_P4") (pintype "bidirectional"))
    )
    (net (code "71") (name "/LVDS27_N") (class "Default")
      (node (ref "IC27") (pin "V2") (pinfunction "IO_L16N_T2_34_V2") (pintype "bidirectional"))
    )
    (net (code "72") (name "/LVDS27_P") (class "Default")
      (node (ref "IC27") (pin "V3") (pinfunction "IO_L16P_T2_34_V3") (pintype "bidirectional"))
    )
    (net (code "73") (name "/MEZZ0_IO0") (class "Default")
      (node (ref "IC27") (pin "U16") (pinfunction "IO_L17N_T2_A13_D29_14_U16") (pintype "bidirectional"))
    )
    (net (code "74") (name "/MEZZ0_IO1") (class "Default")
      (node (ref "IC27") (pin "V16") (pinfunction "IO_L18P_T2_A12_D28_14_V16") (pintype "bidirectional"))
    )
    (net (code "75") (name "/MEZZ0_IO2") (class "Default")
      (node (ref "IC27") (pin "V17") (pinfunction "IO_L18N_T2_A11_D27_14_V17") (pintype "bidirectional"))
    )
    (net (code "76") (name "/MEZZ0_IO3") (class "Default")
      (node (ref "IC27") (pin "R13") (pinfunction "IO_L19P_T3_A10_D26_14_R13") (pintype "bidirectional"))
    )
    (net (code "77") (name "/MEZZ0_IO4") (class "Default")
      (node (ref "IC27") (pin "T13") (pinfunction "IO_L19N_T3_A09_D25_VREF_14_T13") (pintype "bidirectional"))
    )
    (net (code "78") (name "/MEZZ0_IO5") (class "Default")
      (node (ref "IC27") (pin "U14") (pinfunction "IO_L20P_T3_A08_D24_14_U14") (pintype "bidirectional"))
    )
    (net (code "79") (name "/MEZZ0_IO6") (class "Default")
      (node (ref "IC27") (pin "V14") (pinfunction "IO_L20N_T3_A07_D23_14_V14") (pintype "bidirectional"))
    )
    (net (code "80") (name "/MEZZ0_IO7") (class "Default")
      (node (ref "IC27") (pin "V12") (pinfunction "IO_L21P_T3_DQS_14_V12") (pintype "bidirectional"))
    )
    (net (code "81") (name "/MEZZ0_IO8") (class "Default")
      (node (ref "IC27") (pin "V13") (pinfunction "IO_L21N_T3_DQS_A06_D22_14_V13") (pintype "bidirectional"))
    )
    (net (code "82") (name "/MEZZ0_IO9") (class "Default")
      (node (ref "IC27") (pin "T12") (pinfunction "IO_L22P_T3_A05_D21_14_T12") (pintype "bidirectional"))
    )
    (net (code "83") (name "/MEZZ0_IO10") (class "Default")
      (node (ref "IC27") (pin "U12") (pinfunction "IO_L22N_T3_A04_D20_14_U12") (pintype "bidirectional"))
    )
    (net (code "84") (name "/MEZZ0_IO11") (class "Default")
      (node (ref "IC27") (pin "U11") (pinfunction "IO_L23P_T3_A03_D19_14_U11") (pintype "bidirectional"))
    )
    (net (code "85") (name "/MEZZ0_IO12") (class "Default")
      (node (ref "IC27") (pin "V11") (pinfunction "IO_L23N_T3_A02_D18_14_V11") (pintype "bidirectional"))
    )
    (net (code "86") (name "/MEZZ0_IO13") (class "Default")
      (node (ref "IC27") (pin "U9") (pinfunction "IO_L24P_T3_A01_D17_14_U9") (pintype "bidirectional"))
    )
    (net (code "87") (name "/MEZZ0_IO14") (class "Default")
      (node (ref "IC27") (pin "V9") (pinfunction "IO_L24N_T3_A00_D16_14_V9") (pintype "bidirectional"))
    )
    (net (code "88") (name "/MEZZ0_IO15") (class "Default")
      (node (ref "IC27") (pin "U10") (pinfunction "IO_25_14_U10") (pintype "bidirectional"))
    )
    (net (code "90") (name "/MEZZ0_LVDS0_N") (class "Default")
      (node (ref "IC27") (pin "E18") (pinfunction "IO_L24N_T3_RS0_15_E18") (pintype "bidirectional"))
    )
    (net (code "91") (name "/MEZZ0_LVDS0_P") (class "Default")
      (node (ref "IC27") (pin "F17") (pinfunction "IO_L24P_T3_RS1_15_F17") (pintype "bidirectional"))
    )
    (net (code "92") (name "/MEZZ0_LVDS1_N") (class "Default")
      (node (ref "IC27") (pin "F18") (pinfunction "IO_L19N_T3_A21_VREF_15_F18") (pintype "bidirectional"))
    )
    (net (code "93") (name "/MEZZ0_LVDS1_P") (class "Default")
      (node (ref "IC27") (pin "G17") (pinfunction "IO_L19P_T3_A22_15_G17") (pintype "bidirectional"))
    )
    (net (code "94") (name "/MEZZ0_LVDS2_N") (class "Default")
      (node (ref "IC27") (pin "H18") (pinfunction "IO_L23N_T3_FWE_B_15_H18") (pintype "bidirectional"))
    )
    (net (code "95") (name "/MEZZ0_LVDS2_P") (class "Default")
      (node (ref "IC27") (pin "H17") (pinfunction "IO_L23P_T3_FOE_B_15_H17") (pintype "bidirectional"))
    )
    (net (code "96") (name "/MEZZ0_LVDS3_N") (class "Default")
      (node (ref "IC27") (pin "F15") (pinfunction "IO_L21N_T3_DQS_A18_15_F15") (pintype "bidirectional"))
    )
    (net (code "97") (name "/MEZZ0_LVDS3_P") (class "Default")
      (node (ref "IC27") (pin "G15") (pinfunction "IO_L21P_T3_DQS_15_G15") (pintype "bidirectional"))
    )
    (net (code "98") (name "/MEZZ0_LVDS4_N") (class "Default")
      (node (ref "IC27") (pin "F14") (pinfunction "IO_L22N_T3_A16_15_F14") (pintype "bidirectional"))
    )
    (net (code "99") (name "/MEZZ0_LVDS4_P") (class "Default")
      (node (ref "IC27") (pin "G14") (pinfunction "IO_L22P_T3_A17_15_G14") (pintype "bidirectional"))
    )
    (net (code "100") (name "/MEZZ0_LVDS5_N") (class "Default")
      (node (ref "IC27") (pin "D18") (pinfunction "IO_L17N_T2_A25_15_D18") (pintype "bidirectional"))
    )
    (net (code "101") (name "/MEZZ0_LVDS5_P") (class "Default")
      (node (ref "IC27") (pin "E17") (pinfunction "IO_L17P_T2_A26_15_E17") (pintype "bidirectional"))
    )
    (net (code "102") (name "/MEZZ0_LVDS6_N") (class "Default")
      (node (ref "IC27") (pin "C18") (pinfunction "IO_L18N_T2_A23_15_C18") (pintype "bidirectional"))
    )
    (net (code "103") (name "/MEZZ0_LVDS6_P") (class "Default")
      (node (ref "IC27") (pin "C17") (pinfunction "IO_L18P_T2_A24_15_C17") (pintype "bidirectional"))
    )
    (net (code "104") (name "/MEZZ0_LVDS7_N") (class "Default")
      (node (ref "IC27") (pin "G16") (pinfunction "IO_L20N_T3_A19_15_G16") (pintype "bidirectional"))
    )
    (net (code "105") (name "/MEZZ0_LVDS7_P") (class "Default")
      (node (ref "IC27") (pin "H16") (pinfunction "IO_L20P_T3_A20_15_H16") (pintype "bidirectional"))
    )
    (net (code "106") (name "/MEZZ1_IO0") (class "Default")
      (node (ref "IC27") (pin "J16") (pinfunction "IO_L2N_T0_D03_14_J16") (pintype "bidirectional"))
    )
    (net (code "107") (name "/MEZZ1_IO1") (class "Default")
      (node (ref "IC27") (pin "K18") (pinfunction "IO_L3N_T0_DQS_EMCCLK_14_K18") (pintype "bidirectional"))
    )
    (net (code "108") (name "/MEZZ1_IO2") (class "Default")
      (node (ref "IC27") (pin "K17") (pinfunction "IO_L4P_T0_D04_14_K17") (pintype "bidirectional"))
    )
    (net (code "109") (name "/MEZZ1_IO3") (class "Default")
      (node (ref "IC27") (pin "L18") (pinfunction "IO_L4N_T0_D05_14_L18") (pintype "bidirectional"))
    )
    (net (code "110") (name "/MEZZ1_IO4") (class "Default")
      (node (ref "IC27") (pin "J14") (pinfunction "IO_L5P_T0_D06_14_J14") (pintype "bidirectional"))
    )
    (net (code "111") (name "/MEZZ1_IO5") (class "Default")
      (node (ref "IC27") (pin "K15") (pinfunction "IO_L5N_T0_D07_14_K15") (pintype "bidirectional"))
    )
    (net (code "112") (name "/MEZZ1_IO6") (class "Default")
      (node (ref "IC27") (pin "L15") (pinfunction "IO_L6P_T0_FCS_B_14_L15") (pintype "bidirectional"))
    )
    (net (code "113") (name "/MEZZ1_IO7") (class "Default")
      (node (ref "IC27") (pin "M15") (pinfunction "IO_L6N_T0_D08_VREF_14_M15") (pintype "bidirectional"))
    )
    (net (code "114") (name "/MEZZ1_IO8") (class "Default")
      (node (ref "IC27") (pin "M16") (pinfunction "IO_L7P_T1_D09_14_M16") (pintype "bidirectional"))
    )
    (net (code "115") (name "/MEZZ1_IO9") (class "Default")
      (node (ref "IC27") (pin "M17") (pinfunction "IO_L7N_T1_D10_14_M17") (pintype "bidirectional"))
    )
    (net (code "116") (name "/MEZZ1_IO10") (class "Default")
      (node (ref "IC27") (pin "M14") (pinfunction "IO_L8P_T1_D11_14_M14") (pintype "bidirectional"))
    )
    (net (code "117") (name "/MEZZ1_IO11") (class "Default")
      (node (ref "IC27") (pin "N14") (pinfunction "IO_L8N_T1_D12_14_N14") (pintype "bidirectional"))
    )
    (net (code "118") (name "/MEZZ1_IO12") (class "Default")
      (node (ref "IC27") (pin "N16") (pinfunction "IO_L9P_T1_DQS_14_N16") (pintype "bidirectional"))
    )
    (net (code "119") (name "/MEZZ1_IO13") (class "Default")
      (node (ref "IC27") (pin "N17") (pinfunction "IO_L9N_T1_DQS_D13_14_N17") (pintype "bidirectional"))
    )
    (net (code "120") (name "/MEZZ1_IO14") (class "Default")
      (node (ref "IC27") (pin "N18") (pinfunction "IO_L10P_T1_D14_14_N18") (pintype "bidirectional"))
    )
    (net (code "121") (name "/MEZZ1_IO15") (class "Default")
      (node (ref "IC27") (pin "P18") (pinfunction "IO_L10N_T1_D15_14_P18") (pintype "bidirectional"))
    )
    (net (code "123") (name "/MEZZ1_LVDS0_N") (class "Default")
      (node (ref "IC27") (pin "A14") (pinfunction "IO_L8N_T1_AD10N_15_A14") (pintype "bidirectional"))
    )
    (net (code "124") (name "/MEZZ1_LVDS0_P") (class "Default")
      (node (ref "IC27") (pin "A13") (pinfunction "IO_L8P_T1_AD10P_15_A13") (pintype "bidirectional"))
    )
    (net (code "125") (name "/MEZZ1_LVDS1_N") (class "Default")
      (node (ref "IC27") (pin "A12") (pinfunction "IO_L7N_T1_AD2N_15_A12") (pintype "bidirectional"))
    )
    (net (code "126") (name "/MEZZ1_LVDS1_P") (class "Default")
      (node (ref "IC27") (pin "B12") (pinfunction "IO_L7P_T1_AD2P_15_B12") (pintype "bidirectional"))
    )
    (net (code "127") (name "/MEZZ1_LVDS2_N") (class "Default")
      (node (ref "IC27") (pin "C12") (pinfunction "IO_L6N_T0_VREF_15_C12") (pintype "bidirectional"))
    )
    (net (code "128") (name "/MEZZ1_LVDS2_P") (class "Default")
      (node (ref "IC27") (pin "D11") (pinfunction "IO_L6P_T0_15_D11") (pintype "bidirectional"))
    )
    (net (code "129") (name "/MEZZ1_LVDS3_N") (class "Default")
      (node (ref "IC27") (pin "A10") (pinfunction "IO_L5N_T0_AD9N_15_A10") (pintype "bidirectional"))
    )
    (net (code "130") (name "/MEZZ1_LVDS3_P") (class "Default")
      (node (ref "IC27") (pin "B10") (pinfunction "IO_L5P_T0_AD9P_15_B10") (pintype "bidirectional"))
    )
    (net (code "131") (name "/MEZZ1_LVDS4_N") (class "Default")
      (node (ref "IC27") (pin "B11") (pinfunction "IO_L4N_T0_15_B11") (pintype "bidirectional"))
    )
    (net (code "132") (name "/MEZZ1_LVDS4_P") (class "Default")
      (node (ref "IC27") (pin "C11") (pinfunction "IO_L4P_T0_15_C11") (pintype "bidirectional"))
    )
    (net (code "133") (name "/MEZZ1_LVDS5_N") (class "Default")
      (node (ref "IC27") (pin "A9") (pinfunction "IO_L3N_T0_DQS_AD1N_15_A9") (pintype "bidirectional"))
    )
    (net (code "134") (name "/MEZZ1_LVDS5_P") (class "Default")
      (node (ref "IC27") (pin "B9") (pinfunction "IO_L3P_T0_DQS_AD1P_15_B9") (pintype "bidirectional"))
    )
    (net (code "135") (name "/MEZZ1_LVDS6_N") (class "Default")
      (node (ref "IC27") (pin "C9") (pinfunction "IO_L2N_T0_AD8N_15_C9") (pintype "bidirectional"))
    )
    (net (code "136") (name "/MEZZ1_LVDS6_P") (class "Default")
      (node (ref "IC27") (pin "D9") (pinfunction "IO_L2P_T0_AD8P_15_D9") (pintype "bidirectional"))
    )
    (net (code "137") (name "/MEZZ1_LVDS7_N") (class "Default")
      (node (ref "IC27") (pin "C8") (pinfunction "IO_L1N_T0_AD0N_15_C8") (pintype "bidirectional"))
    )
    (net (code "138") (name "/MEZZ1_LVDS7_P") (class "Default")
      (node (ref "IC27") (pin "D8") (pinfunction "IO_L1P_T0_AD0P_15_D8") (pintype "bidirectional"))
    )
    (net (code "139") (name "/Main_DCXO_OE") (class "Default")
      (node (ref "IC14") (pin "10") (pinfunction "B1_10") (pintype "bidirectional"))
    )
    (net (code "140") (name "/Main_DCXO_OE_2V5") (class "Default")
      (node (ref "IC14") (pin "2") (pinfunction "A1_2") (pintype "bidirectional"))
      (node (ref "IC27") (pin "N6") (pinfunction "IO_L8N_T1_34_N6") (pintype "bidirectional"))
    )
    (net (code "141") (name "/Main_DCXO_SCL") (class "Default")
      (node (ref "IC27") (pin "P14") (pinfunction "IO_L12P_T1_MRCC_14_P14") (pintype "bidirectional"))
    )
    (net (code "142") (name "/Main_DCXO_SDA") (class "Default")
      (node (ref "IC27") (pin "U15") (pinfunction "IO_L17P_T2_A14_D30_14_U15") (pintype "bidirectional"))
    )
    (net (code "143") (name "/REC_CLOCK_N") (class "Default")
      (node (ref "IC27") (pin "M1") (pinfunction "IO_L7N_T1_34_M1") (pintype "bidirectional"))
    )
    (net (code "144") (name "/REC_CLOCK_P") (class "Default")
      (node (ref "IC27") (pin "M2") (pinfunction "IO_L7P_T1_34_M2") (pintype "bidirectional"))
    )
    (net (code "145") (name "/REF2_N") (class "Default")
      (node (ref "IC27") (pin "D15") (pinfunction "IO_L13N_T2_MRCC_15_D15") (pintype "bidirectional"))
      (node (ref "R144") (pin "1") (pinfunction "1_1") (pintype "passive"))
    )
    (net (code "146") (name "/REF2_P") (class "Default")
      (node (ref "IC27") (pin "E15") (pinfunction "IO_L13P_T2_MRCC_15_E15") (pintype "bidirectional"))
      (node (ref "R146") (pin "1") (pinfunction "1_1") (pintype "passive"))
    )
    (net (code "147") (name "/REF_CLK_SRC_EXT_SEL") (class "Default")
      (node (ref "IC6") (pin "10") (pinfunction "B1_10") (pintype "bidirectional"))
    )
    (net (code "148") (name "/REF_CLK_SRC_EXT_SEL_2V5") (class "Default")
      (node (ref "IC27") (pin "R6") (pinfunction "IO_25_34_R6") (pintype "bidirectional"))
      (node (ref "IC6") (pin "2") (pinfunction "A1_2") (pintype "bidirectional"))
    )
    (net (code "149") (name "/RESET_Rn") (class "Default")
      (node (ref "IC27") (pin "L3") (pinfunction "IO_L5N_T0_34_L3") (pintype "bidirectional"))
      (node (ref "R46") (pin "2") (pinfunction "2_2") (pintype "passive"))
    )
    (net (code "150") (name "/RESETn") (class "Default")
      (node (ref "R46") (pin "1") (pinfunction "1_1") (pintype "passive"))
    )
    (net (code "151") (name "/RTM_FPGA_CFG.FPGA_CFG_CCLK") (class "Default")
      (node (ref "IC27") (pin "E8") (pinfunction "CCLK_0_E8") (pintype "bidirectional"))
    )
    (net (code "152") (name "/RTM_FPGA_CFG.FPGA_CFG_DIN") (class "Default")
      (node (ref "IC27") (pin "L17") (pinfunction "IO_L1N_T0_D01_DIN_14_L17") (pintype "bidirectional"))
    )
    (net (code "153") (name "/RTM_FPGA_CFG.FPGA_CFG_DONE") (class "Default")
      (node (ref "IC27") (pin "F12") (pinfunction "DONE_0_F12") (pintype "bidirectional"))
      (node (ref "T8") (pin "1") (pinfunction "G_1") (pintype "passive"))
    )
    (net (code "154") (name "/RTM_FPGA_CFG.FPGA_CFG_INIT_B") (class "Default")
      (node (ref "IC27") (pin "T10") (pinfunction "INIT_B_0_T10") (pintype "bidirectional"))
    )
    (net (code "155") (name "/RTM_FPGA_CFG.FPGA_CFG_PROGRAM_B") (class "Default")
      (node (ref "IC27") (pin "P10") (pinfunction "PROGRAM_B_0_P10") (pintype "input"))
    )
    (net (code "156") (name "/RTM_FPGA_SCL") (class "Default")
      (node (ref "IC27") (pin "P15") (pinfunction "IO_L11P_T1_SRCC_14_P15") (pintype "bidirectional"))
    )
    (net (code "157") (name "/RTM_FPGA_SDA") (class "Default")
      (node (ref "IC27") (pin "P16") (pinfunction "IO_L11N_T1_SRCC_14_P16") (pintype "bidirectional"))
    )
    (net (code "158") (name "/RTM_FPGA_SYSREF0_N") (class "Default")
      (node (ref "IC27") (pin "T2") (pinfunction "IO_L14N_T2_SRCC_34_T2") (pintype "bidirectional"))
    )
    (net (code "159") (name "/RTM_FPGA_SYSREF0_P") (class "Default")
      (node (ref "IC27") (pin "R3") (pinfunction "IO_L14P_T2_SRCC_34_R3") (pintype "bidirectional"))
    )
    (net (code "160") (name "/RTM_FPGA_SYSREF1_N") (class "Default")
      (node (ref "IC27") (pin "T5") (pinfunction "IO_L21N_T3_DQS_34_T5") (pintype "bidirectional"))
    )
    (net (code "161") (name "/RTM_FPGA_SYSREF1_P") (class "Default")
      (node (ref "IC27") (pin "R5") (pinfunction "IO_L21P_T3_DQS_34_R5") (pintype "bidirectional"))
    )
    (net (code "162") (name "/RTM_UART_Rx") (class "Default")
      (node (ref "IC27") (pin "U17") (pinfunction "IO_L16N_T2_A15_D31_14_U17") (pintype "bidirectional"))
    )
    (net (code "163") (name "/RTM_UART_Tx") (class "Default")
      (node (ref "IC27") (pin "T17") (pinfunction "IO_L16P_T2_CSI_B_14_T17") (pintype "bidirectional"))
    )
    (net (code "164") (name "/SI5324_INT_ALM") (class "Default")
      (node (ref "R31") (pin "1") (pinfunction "1_1") (pintype "passive"))
    )
    (net (code "165") (name "/SI5324_INT_ALM_2V5") (class "Default")
      (node (ref "IC27") (pin "V6") (pinfunction "IO_L23N_T3_34_V6") (pintype "bidirectional"))
      (node (ref "R31") (pin "2") (pinfunction "2_2") (pintype "passive"))
    )
    (net (code "166") (name "/SI5324_RST") (class "Default")
      (node (ref "IC14") (pin "7") (pinfunction "B4_7") (pintype "bidirectional"))
    )
    (net (code "167") (name "/SI5324_RST_2V5") (class "Default")
      (node (ref "IC14") (pin "5") (pinfunction "A4_5") (pintype "bidirectional"))
      (node (ref "IC27") (pin "L5") (pinfunction "IO_L6P_T0_34_L5") (pintype "bidirectional"))
    )
    (net (code "168") (name "/TCK") (class "Default")
      (node (ref "IC27") (pin "F8") (pinfunction "TCK_0_F8") (pintype "input"))
    )
    (net (code "169") (name "/TDI") (class "Default")
      (node (ref "IC27") (pin "T9") (pinfunction "TDI_0_T9") (pintype "input"))
    )
    (net (code "170") (name "/TDO") (class "Default")
      (node (ref "IC27") (pin "T8") (pinfunction "TDO_0_T8") (pintype "output"))
    )
    (net (code "171") (name "/TMS") (class "Default")
      (node (ref "IC27") (pin "R8") (pinfunction "TMS_0_R8") (pintype "input"))
    )
    (net (code "172") (name "/Vbias_1.25V") (class "Default")
      (node (ref "C104") (pin "1") (pinfunction "1_1") (pintype "passive"))
      (node (ref "C105") (pin "1") (pinfunction "1_1") (pintype "passive"))
      (node (ref "C157") (pin "1") (pinfunction "1_1") (pintype "passive"))
      (node (ref "C167") (pin "1") (pinfunction "1_1") (pintype "passive"))
      (node (ref "R125") (pin "1") (pinfunction "1_1") (pintype "passive"))
      (node (ref "R144") (pin "2") (pinfunction "2_2") (pintype "passive"))
      (node (ref "R146") (pin "2") (pinfunction "2_2") (pintype "passive"))
      (node (ref "R179") (pin "2") (pinfunction "2_2") (pintype "passive"))
      (node (ref "R180") (pin "2") (pinfunction "2_2") (pintype "passive"))
      (node (ref "R244") (pin "1") (pinfunction "1_1") (pintype "passive"))
      (node (ref "R245") (pin "1") (pinfunction "1_1") (pintype "passive"))
      (node (ref "R47") (pin "2") (pinfunction "2_2") (pintype "passive"))
      (node (ref "R48") (pin "2") (pinfunction "2_2") (pintype "passive"))
      (node (ref "R60") (pin "1") (pinfunction "1_1") (pintype "passive"))
    )
    (net (code "173") (name "/WR_CLK_SEL") (class "Default")
      (node (ref "IC14") (pin "8") (pinfunction "B3_8") (pintype "bidirectional"))
    )
    (net (code "174") (name "/WR_CLK_SEL_2V5") (class "Default")
      (node (ref "IC14") (pin "4") (pinfunction "A3_4") (pintype "bidirectional"))
      (node (ref "IC27") (pin "M5") (pinfunction "IO_L6N_T0_VREF_34_M5") (pintype "bidirectional"))
    )
    (net (code "185") (name "GND") (class "Default")
      (node (ref "C104") (pin "2") (pinfunction "2_2") (pintype "passive"))
      (node (ref "C105") (pin "2") (pinfunction "2_2") (pintype "passive"))
      (node (ref "C114") (pin "2") (pinfunction "2_2") (pintype "passive"))
      (node (ref "C115") (pin "2") (pinfunction "2_2") (pintype "passive"))
      (node (ref "C116") (pin "2") (pinfunction "2_2") (pintype "passive"))
      (node (ref "C117") (pin "2") (pinfunction "2_2") (pintype "passive"))
      (node (ref "C149") (pin "1") (pinfunction "1_1") (pintype "passive"))
      (node (ref "C157") (pin "2") (pinfunction "2_2") (pintype "passive"))
      (node (ref "C167") (pin "2") (pinfunction "2_2") (pintype "passive"))
      (node (ref "IC14") (pin "6") (pinfunction "GND_6") (pintype "power_in"))
      (node (ref "IC27") (pin "K10") (pinfunction "VP_0_K10") (pintype "input"))
      (node (ref "IC27") (pin "K9") (pinfunction "VREFN_0_K9") (pintype "input"))
      (node (ref "IC27") (pin "L10") (pinfunction "VREFP_0_L10") (pintype "input"))
      (node (ref "IC27") (pin "L9") (pinfunction "VN_0_L9") (pintype "input"))
      (node (ref "IC6") (pin "6") (pinfunction "GND_6") (pintype "power_in"))
      (node (ref "J14") (pin "2") (pinfunction "2_2") (pintype "bidirectional"))
      (node (ref "J15") (pin "12") (pinfunction "12_12") (pintype "bidirectional"))
      (node (ref "J17") (pin "2") (pinfunction "2_2") (pintype "bidirectional"))
      (node (ref "OSC1") (pin "2") (pinfunction "GND_2") (pintype "power_in"))
      (node (ref "R40") (pin "1") (pinfunction "1_1") (pintype "passive"))
      (node (ref "R41") (pin "1") (pinfunction "1_1") (pintype "passive"))
      (node (ref "R42") (pin "1") (pinfunction "1_1") (pintype "passive"))
      (node (ref "R47") (pin "1") (pinfunction "1_1") (pintype "passive"))
      (node (ref "R51") (pin "1") (pinfunction "1_1") (pintype "passive"))
      (node (ref "R53") (pin "1") (pinfunction "1_1") (pintype "passive"))
      (node (ref "T1") (pin "2") (pinfunction "S_2") (pintype "passive"))
      (node (ref "T8") (pin "2") (pinfunction "S_2") (pintype "passive"))
    )
    (net (code "186") (name "Net-(C152-Pad1)") (class "Default")
      (node (ref "C152") (pin "1") (pinfunction "1_1") (pintype "passive"))
      (node (ref "J14") (pin "1") (pinfunction "1_1") (pintype "bidirectional"))
      (node (ref "R143") (pin "1") (pinfunction "1_1") (pintype "passive"))
    )
    (net (code "187") (name "Net-(C152-Pad2)") (class "Default")
      (node (ref "C152") (pin "2") (pinfunction "2_2") (pintype "passive"))
      (node (ref "R145") (pin "1") (pinfunction "1_1") (pintype "passive"))
    )
    (net (code "188") (name "Net-(C153-Pad1)") (class "Default")
      (node (ref "C153") (pin "1") (pinfunction "1_1") (pintype "passive"))
      (node (ref "J17") (pin "1") (pinfunction "1_1") (pintype "bidirectional"))
      (node (ref "R143") (pin "2") (pinfunction "2_2") (pintype "passive"))
    )
    (net (code "189") (name "Net-(C153-Pad2)") (class "Default")
      (node (ref "C153") (pin "2") (pinfunction "2_2") (pintype "passive"))
      (node (ref "R147") (pin "2") (pinfunction "2_2") (pintype "passive"))
    )
    (net (code "190") (name "Net-(IC27D-CFGBVS_0)") (class "Default")
      (node (ref "IC27") (pin "E12") (pinfunction "CFGBVS_0_E12") (pintype "input"))
      (node (ref "R36") (pin "2") (pinfunction "2_2") (pintype "passive"))
    )
    (net (code "191") (name "Net-(IC27D-M0_0)") (class "Default")
      (node (ref "IC27") (pin "R12") (pinfunction "M0_0_R12") (pintype "input"))
      (node (ref "R38") (pin "2") (pinfunction "2_2") (pintype "passive"))
    )
    (net (code "192") (name "Net-(IC27D-M1_0)") (class "Default")
      (node (ref "IC27") (pin "R11") (pinfunction "M1_0_R11") (pintype "input"))
      (node (ref "R34") (pin "2") (pinfunction "2_2") (pintype "passive"))
    )
    (net (code "193") (name "Net-(IC27D-M2_0)") (class "Default")
      (node (ref "IC27") (pin "F13") (pinfunction "M2_0_F13") (pintype "input"))
      (node (ref "R129") (pin "2") (pinfunction "2_2") (pintype "passive"))
    )
    (net (code "194") (name "Net-(LD1-A)") (class "Default")
      (node (ref "LD1") (pin "2") (pinfunction "A_2") (pintype "passive"))
      (node (ref "R243") (pin "1") (pinfunction "1_1") (pintype "passive"))
    )
    (net (code "195") (name "Net-(LD1-C)") (class "Default")
      (node (ref "LD1") (pin "1") (pinfunction "C_1") (pintype "passive"))
      (node (ref "T1") (pin "3") (pinfunction "D_3") (pintype "passive"))
    )
    (net (code "196") (name "Net-(LD20-A)") (class "Default")
      (node (ref "LD20") (pin "2") (pinfunction "A_2") (pintype "passive"))
      (node (ref "R74") (pin "1") (pinfunction "1_1") (pintype "passive"))
    )
    (net (code "197") (name "Net-(LD20-C)") (class "Default")
      (node (ref "LD20") (pin "1") (pinfunction "C_1") (pintype "passive"))
      (node (ref "T8") (pin "3") (pinfunction "D_3") (pintype "passive"))
    )
    (net (code "198") (name "Net-(OSC1-OUT)") (class "Default")
      (node (ref "OSC1") (pin "3") (pinfunction "OUT_3") (pintype "output"))
      (node (ref "R37") (pin "1") (pinfunction "1_1") (pintype "passive"))
    )
    (net (code "199") (name "P2V5F") (class "Default")
      (node (ref "C114") (pin "1") (pinfunction "1_1") (pintype "passive"))
      (node (ref "C116") (pin "1") (pinfunction "1_1") (pintype "passive"))
      (node (ref "IC14") (pin "1") (pinfunction "VCCA_1") (pintype "power_in"))
      (node (ref "IC14") (pin "12") (pinfunction "OE_12") (pintype "input"))
      (node (ref "IC6") (pin "1") (pinfunction "VCCA_1") (pintype "power_in"))
      (node (ref "IC6") (pin "12") (pinfunction "OE_12") (pintype "input"))
      (node (ref "J15") (pin "11") (pinfunction "11_11") (pintype "bidirectional"))
      (node (ref "R43") (pin "1") (pinfunction "1_1") (pintype "passive"))
      (node (ref "R44") (pin "1") (pinfunction "1_1") (pintype "passive"))
      (node (ref "R45") (pin "1") (pinfunction "1_1") (pintype "passive"))
      (node (ref "R48") (pin "1") (pinfunction "1_1") (pintype "passive"))
      (node (ref "R49") (pin "1") (pinfunction "1_1") (pintype "passive"))
    )
    (net (code "200") (name "P3V3F") (class "Default")
      (node (ref "C115") (pin "1") (pinfunction "1_1") (pintype "passive"))
      (node (ref "C117") (pin "1") (pinfunction "1_1") (pintype "passive"))
      (node (ref "C149") (pin "2") (pinfunction "2_2") (pintype "passive"))
      (node (ref "IC14") (pin "11") (pinfunction "VCCB_11") (pintype "power_in"))
      (node (ref "IC6") (pin "11") (pinfunction "VCCB_11") (pintype "power_in"))
      (node (ref "OSC1") (pin "1") (pinfunction "OE_1") (pintype "input"))
      (node (ref "OSC1") (pin "4") (pinfunction "VCC_4") (pintype "power_in"))
      (node (ref "R129") (pin "1") (pinfunction "1_1") (pintype "passive"))
      (node (ref "R243") (pin "2") (pinfunction "2_2") (pintype "passive"))
      (node (ref "R34") (pin "1") (pinfunction "1_1") (pintype "passive"))
      (node (ref "R36") (pin "1") (pinfunction "1_1") (pintype "passive"))
      (node (ref "R38") (pin "1") (pinfunction "1_1") (pintype "passive"))
      (node (ref "R52") (pin "1") (pinfunction "1_1") (pintype "passive"))
      (node (ref "R74") (pin "2") (pinfunction "2_2") (pintype "passive"))
    )
    (net (code "201") (name "unconnected-(IC6-A4-Pad5)") (class "Default")
      (node (ref "IC6") (pin "5") (pinfunction "A4_5") (pintype "bidirectional+no_connect"))
    )
    (net (code "202") (name "unconnected-(IC6-B4-Pad7)") (class "Default")
      (node (ref "IC6") (pin "7") (pinfunction "B4_7") (pintype "bidirectional+no_connect"))
    )
    (net (code "203") (name "unconnected-(IC27B-IO_0_15-PadD10)") (class "Default")
      (node (ref "IC27") (pin "D10") (pinfunction "IO_0_15_D10") (pintype "bidirectional+no_connect"))
    )
    (net (code "204") (name "unconnected-(IC27B-IO_25_15-PadH14)") (class "Default")
      (node (ref "IC27") (pin "H14") (pinfunction "IO_25_15_H14") (pintype "bidirectional+no_connect"))
    )
    (net (code "205") (name "unconnected-(IC27B-IO_L9N_T1_DQS_AD3N_15-PadB15)") (class "Default")
      (node (ref "IC27") (pin "B15") (pinfunction "IO_L9N_T1_DQS_AD3N_15_B15") (pintype "bidirectional"))
    )
    (net (code "206") (name "unconnected-(IC27B-IO_L9P_T1_DQS_AD3P_15-PadC14)") (class "Default")
      (node (ref "IC27") (pin "C14") (pinfunction "IO_L9P_T1_DQS_AD3P_15_C14") (pintype "bidirectional"))
    )
    (net (code "207") (name "unconnected-(IC27C-IO_0_34-PadJ6)") (class "Default")
      (node (ref "IC27") (pin "J6") (pinfunction "IO_0_34_J6") (pintype "bidirectional+no_connect"))
    )
    (net (code "208") (name "unconnected-(IC27C-IO_L1P_T0_34-PadK6)") (class "Default")
      (node (ref "IC27") (pin "K6") (pinfunction "IO_L1P_T0_34_K6") (pintype "bidirectional+no_connect"))
    )
    (net (code "209") (name "unconnected-(IC27C-IO_L22P_T3_34-PadR7)") (class "Default")
      (node (ref "IC27") (pin "R7") (pinfunction "IO_L22P_T3_34_R7") (pintype "bidirectional+no_connect"))
    )
    (net (code "210") (name "unconnected-(IC27C-IO_L23P_T3_34-PadU7)") (class "Default")
      (node (ref "IC27") (pin "U7") (pinfunction "IO_L23P_T3_34_U7") (pintype "bidirectional+no_connect"))
    )
  )
)
